# AEBS_component_FrontV1_2.net
KiCad netlist of a schematic drawn in Altium Designer
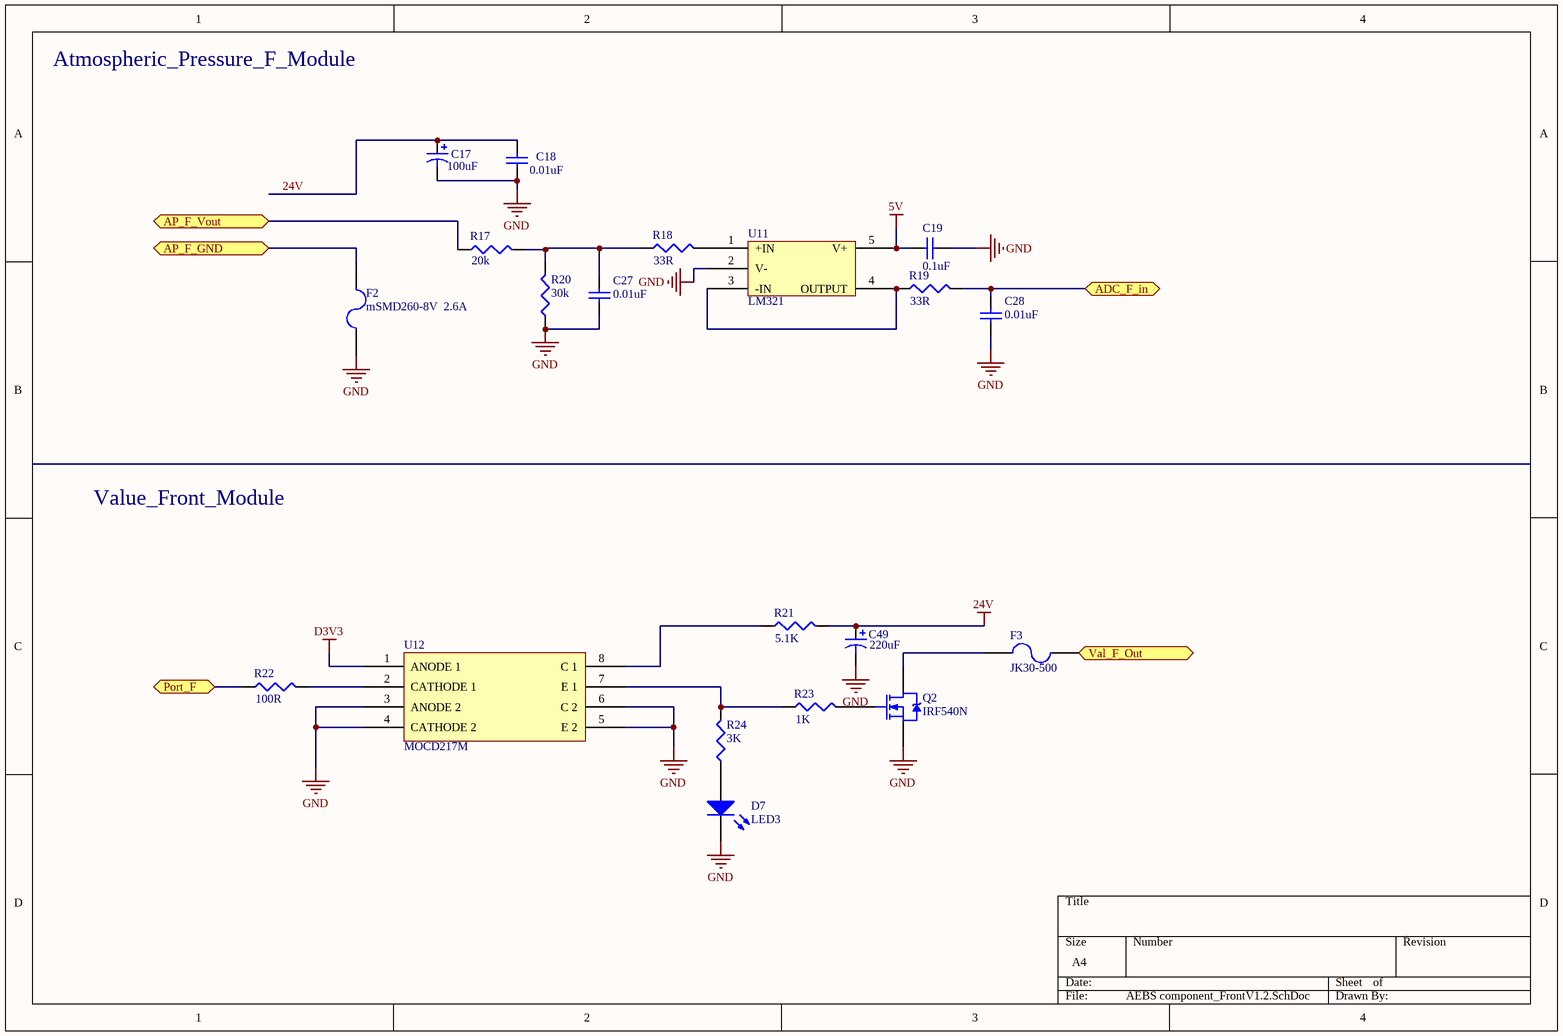
[diagram p0: AEBS component_FrontV1.2.SchDoc]

(export (version "E")
  (design (tool "Eeschema 10.0.6"))
  (components
    (comp (ref "C17")
      (value "100uF")
      (footprint "C0805")
      (description "Polarized Capacitor (Surface Mount)")
      (fields (field (name "Comment") "Cap Pol3") (field (name "PUBLISHER") "Altium Limited"))
      (libsource (lib "Miscellaneous Devices") (part "Cap Pol3"))
    )
    (comp (ref "C18")
      (value "0.01uF")
      (footprint "C1206")
      (description "Capacitor (Semiconductor SIM Model)")
      (fields (field (name "Comment") "Cap Semi") (field (name "PUBLISHER") "Altium Limited"))
      (libsource (lib "Miscellaneous Devices") (part "Cap Semi"))
    )
    (comp (ref "C19")
      (value "0.1uF")
      (footprint "1608[0603]")
      (description "Capacitor (Semiconductor SIM Model)")
      (fields (field (name "Comment") "Cap Semi") (field (name "PUBLISHER") "Altium Limited"))
      (libsource (lib "Miscellaneous Devices") (part "Cap Semi"))
    )
    (comp (ref "C27")
      (value "0.01uF")
      (footprint "1608[0603]")
      (description "Capacitor (Semiconductor SIM Model)")
      (fields (field (name "Comment") "Cap Semi") (field (name "PUBLISHER") "Altium Limited"))
      (libsource (lib "Miscellaneous Devices") (part "Cap Semi"))
    )
    (comp (ref "C28")
      (value "0.01uF")
      (footprint "1608[0603]")
      (description "Capacitor (Semiconductor SIM Model)")
      (fields (field (name "Comment") "Cap Semi") (field (name "PUBLISHER") "Altium Limited"))
      (libsource (lib "Miscellaneous Devices") (part "Cap Semi"))
    )
    (comp (ref "C49")
      (value "220uF")
      (footprint "hg:Cap_pol_8*10.2")
      (description "Polarized Capacitor (Radial)")
      (fields (field (name "Comment") "Cap Pol1") (field (name "PUBLISHER") "Altium Limited"))
      (libsource (lib "Miscellaneous Devices") (part "Cap Pol1"))
    )
    (comp (ref "D7")
      (value "LED3")
      (footprint "hg:1206")
      (description "Typical BLUE SiC LED")
      (fields (field (name "PUBLISHER") "Altium Limited"))
      (libsource (lib "Miscellaneous Devices") (part "LED3"))
    )
    (comp (ref "F2")
      (value "mSMD260-8V  2.6A")
      (footprint "1812")
      (description "Fuse")
      (fields (field (name "PUBLISHER") "Altium Limited"))
      (libsource (lib "Miscellaneous Devices") (part "Fuse 2"))
    )
    (comp (ref "F3")
      (value "JK30-500")
      (footprint "hg:JK30-500")
      (description "Fuse")
      (fields (field (name "PUBLISHER") "Altium Limited"))
      (libsource (lib "Miscellaneous Devices") (part "Fuse 2"))
    )
    (comp (ref "Q2")
      (value "IRF540N")
      (footprint "TO-220AB")
      (description "N-Channel Power MOSFET")
      (fields (field (name "PUBLISHER") "Altium Limited"))
      (libsource (lib "Miscellaneous Devices") (part "NMOS-2"))
    )
    (comp (ref "R17")
      (value "20k")
      (footprint "J1-0603")
      (description "Resistor")
      (fields (field (name "Comment") "Res3") (field (name "PUBLISHER") "Altium Limited"))
      (libsource (lib "Miscellaneous Devices") (part "Res3"))
    )
    (comp (ref "R18")
      (value "33R")
      (footprint "J1-0603")
      (description "Resistor")
      (fields (field (name "Comment") "Res3") (field (name "PUBLISHER") "Altium Limited"))
      (libsource (lib "Miscellaneous Devices") (part "Res3"))
    )
    (comp (ref "R19")
      (value "33R")
      (footprint "J1-0603")
      (description "Resistor")
      (fields (field (name "Comment") "Res3") (field (name "PUBLISHER") "Altium Limited"))
      (libsource (lib "Miscellaneous Devices") (part "Res3"))
    )
    (comp (ref "R20")
      (value "30k")
      (footprint "J1-0603")
      (description "Resistor")
      (fields (field (name "Comment") "Res3") (field (name "PUBLISHER") "Altium Limited"))
      (libsource (lib "Miscellaneous Devices") (part "Res3"))
    )
    (comp (ref "R21")
      (value "5.1K")
      (footprint "J1-0603")
      (description "Resistor")
      (fields (field (name "Comment") "Res3") (field (name "PUBLISHER") "Altium Limited"))
      (libsource (lib "Miscellaneous Devices") (part "Res3"))
    )
    (comp (ref "R22")
      (value "100R")
      (footprint "J1-0603")
      (description "Resistor")
      (fields (field (name "Comment") "Res3") (field (name "PUBLISHER") "Altium Limited"))
      (libsource (lib "Miscellaneous Devices") (part "Res3"))
    )
    (comp (ref "R23")
      (value "1K")
      (footprint "J1-0603")
      (description "Resistor")
      (fields (field (name "Comment") "Res3") (field (name "PUBLISHER") "Altium Limited"))
      (libsource (lib "Miscellaneous Devices") (part "Res3"))
    )
    (comp (ref "R24")
      (value "3K")
      (footprint "J1-0603")
      (description "Resistor")
      (fields (field (name "Comment") "Res3") (field (name "PUBLISHER") "Altium Limited"))
      (libsource (lib "Miscellaneous Devices") (part "Res3"))
    )
    (comp (ref "U11") (value "LM321") (footprint "hg:LM321") (libsource (lib "hg") (part "LM321")))
    (comp (ref "U12") (value "MOCD217M") (footprint "hg:MOCD217M") (libsource (lib "hg") (part "MOCD217M")))
  )
  (nets
    (net (code "1") (name "/ADC_F_in") (class "Default")
      (node (ref "C28") (pin "2") (pinfunction "2_2") (pintype "passive"))
      (node (ref "R19") (pin "2") (pinfunction "2_2") (pintype "passive"))
    )
    (net (code "2") (name "/AP_F_GND") (class "Default")
      (node (ref "F2") (pin "1") (pinfunction "1_1") (pintype "passive"))
    )
    (net (code "3") (name "/AP_F_Vout") (class "Default")
      (node (ref "R17") (pin "1") (pinfunction "1_1") (pintype "passive"))
    )
    (net (code "4") (name "/Port_F") (class "Default")
      (node (ref "R22") (pin "1") (pinfunction "1_1") (pintype "passive"))
    )
    (net (code "5") (name "/Val_F_Out") (class "Default")
      (node (ref "F3") (pin "2") (pinfunction "2_2") (pintype "passive"))
    )
    (net (code "6") (name "5V") (class "Default")
      (node (ref "C19") (pin "2") (pinfunction "2_2") (pintype "passive"))
      (node (ref "U11") (pin "5") (pinfunction "V+_5") (pintype "passive"))
    )
    (net (code "7") (name "24V") (class "Default")
      (node (ref "C17") (pin "1") (pinfunction "1_1") (pintype "passive"))
      (node (ref "C18") (pin "1") (pinfunction "1_1") (pintype "passive"))
      (node (ref "C49") (pin "1") (pinfunction "1_1") (pintype "passive"))
      (node (ref "R21") (pin "2") (pinfunction "2_2") (pintype "passive"))
    )
    (net (code "8") (name "D3V3") (class "Default")
      (node (ref "U12") (pin "1") (pinfunction "ANODE_1_1") (pintype "passive"))
    )
    (net (code "9") (name "GND") (class "Default")
      (node (ref "C17") (pin "2") (pinfunction "2_2") (pintype "passive"))
      (node (ref "C18") (pin "2") (pinfunction "2_2") (pintype "passive"))
      (node (ref "C19") (pin "1") (pinfunction "1_1") (pintype "passive"))
      (node (ref "C27") (pin "1") (pinfunction "1_1") (pintype "passive"))
      (node (ref "C28") (pin "1") (pinfunction "1_1") (pintype "passive"))
      (node (ref "C49") (pin "2") (pinfunction "2_2") (pintype "passive"))
      (node (ref "D7") (pin "2") (pinfunction "K_2") (pintype "passive"))
      (node (ref "F2") (pin "2") (pinfunction "2_2") (pintype "passive"))
      (node (ref "Q2") (pin "3") (pinfunction "S_3") (pintype "passive"))
      (node (ref "R20") (pin "1") (pinfunction "1_1") (pintype "passive"))
      (node (ref "U11") (pin "2") (pinfunction "V-_2") (pintype "passive"))
      (node (ref "U12") (pin "3") (pinfunction "ANODE_2_3") (pintype "passive"))
      (node (ref "U12") (pin "4") (pinfunction "CATHODE_2_4") (pintype "passive"))
      (node (ref "U12") (pin "5") (pinfunction "E_2_5") (pintype "passive"))
      (node (ref "U12") (pin "6") (pinfunction "C_2_6") (pintype "passive"))
    )
    (net (code "10") (name "Net-(C27-Pad2)") (class "Default")
      (node (ref "C27") (pin "2") (pinfunction "2_2") (pintype "passive"))
      (node (ref "R17") (pin "2") (pinfunction "2_2") (pintype "passive"))
      (node (ref "R18") (pin "1") (pinfunction "1_1") (pintype "passive"))
      (node (ref "R20") (pin "2") (pinfunction "2_2") (pintype "passive"))
    )
    (net (code "11") (name "Net-(D7-A)") (class "Default")
      (node (ref "D7") (pin "1") (pinfunction "A_1") (pintype "passive"))
      (node (ref "R24") (pin "1") (pinfunction "1_1") (pintype "passive"))
    )
    (net (code "12") (name "Net-(Q2-D)") (class "Default")
      (node (ref "F3") (pin "1") (pinfunction "1_1") (pintype "passive"))
      (node (ref "Q2") (pin "2") (pinfunction "D_2") (pintype "passive"))
    )
    (net (code "13") (name "Net-(Q2-G)") (class "Default")
      (node (ref "Q2") (pin "1") (pinfunction "G_1") (pintype "passive"))
      (node (ref "R23") (pin "2") (pinfunction "2_2") (pintype "passive"))
    )
    (net (code "14") (name "Net-(U11-+IN)") (class "Default")
      (node (ref "R18") (pin "2") (pinfunction "2_2") (pintype "passive"))
      (node (ref "U11") (pin "1") (pinfunction "+IN_1") (pintype "passive"))
    )
    (net (code "15") (name "Net-(U11--IN)") (class "Default")
      (node (ref "R19") (pin "1") (pinfunction "1_1") (pintype "passive"))
      (node (ref "U11") (pin "3") (pinfunction "-IN_3") (pintype "passive"))
      (node (ref "U11") (pin "4") (pinfunction "OUTPUT_4") (pintype "passive"))
    )
    (net (code "16") (name "Net-(U12-CATHODE_1)") (class "Default")
      (node (ref "R22") (pin "2") (pinfunction "2_2") (pintype "passive"))
      (node (ref "U12") (pin "2") (pinfunction "CATHODE_1_2") (pintype "passive"))
    )
    (net (code "17") (name "Net-(U12-C_1)") (class "Default")
      (node (ref "R21") (pin "1") (pinfunction "1_1") (pintype "passive"))
      (node (ref "U12") (pin "8") (pinfunction "C_1_8") (pintype "passive"))
    )
    (net (code "18") (name "Net-(U12-E_1)") (class "Default")
      (node (ref "R23") (pin "1") (pinfunction "1_1") (pintype "passive"))
      (node (ref "R24") (pin "2") (pinfunction "2_2") (pintype "passive"))
      (node (ref "U12") (pin "7") (pinfunction "E_1_7") (pintype "passive"))
    )
  )
)
